# control_project.net
KiCad netlist of a schematic drawn in EAGLE
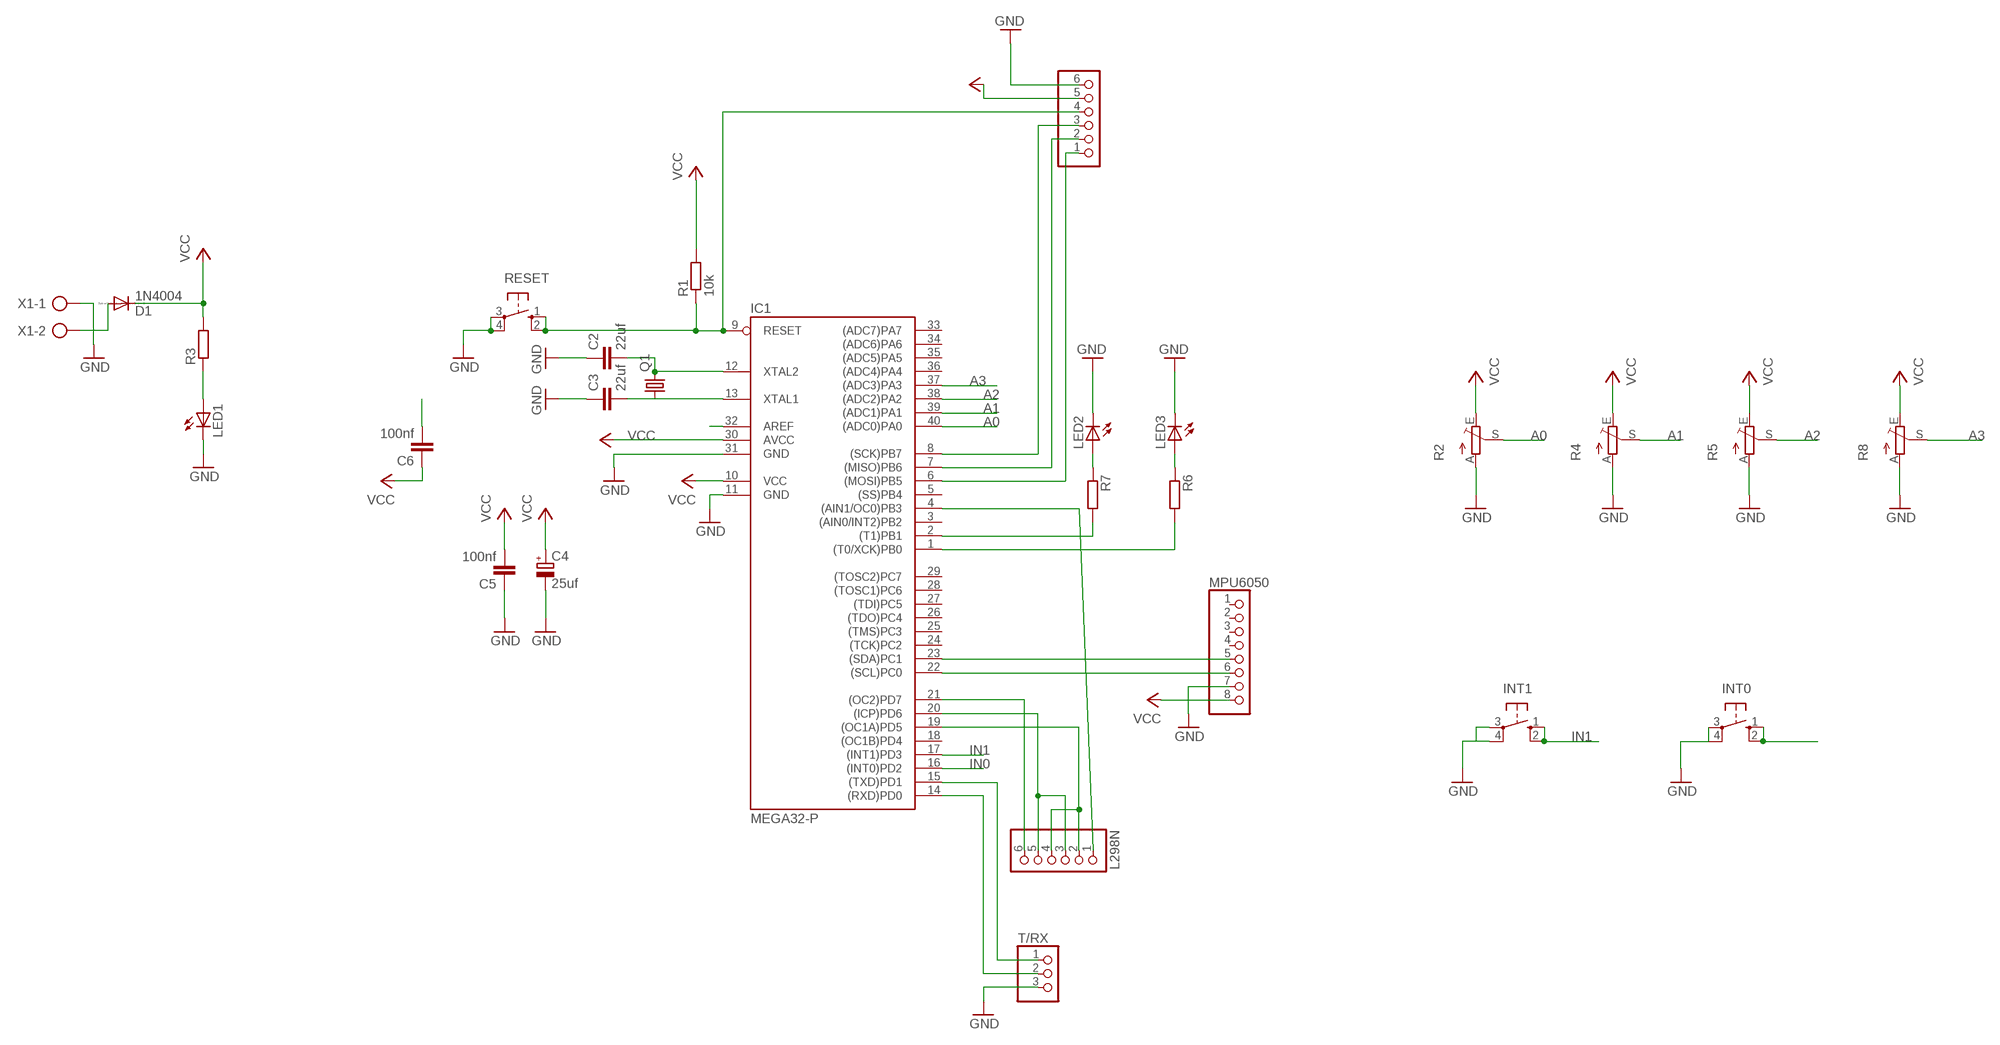
[diagram p0: schematic, sheet 1]

(export (version "E")
  (design (tool "Eeschema 10.0.6"))
  (components
    (comp (ref "C2")
      (value "22uf")
      (footprint "eagle-import:C050-025X075")
      (libsource (lib "eagle-import") (part "C-EU050-025X075"))
    )
    (comp (ref "C3")
      (value "22uf")
      (footprint "eagle-import:C050-025X075")
      (libsource (lib "eagle-import") (part "C-EU050-025X075"))
    )
    (comp (ref "C4")
      (value "25uf")
      (footprint "eagle-import:E1,8-4")
      (libsource (lib "eagle-import") (part "CPOL-EUE1.8-4"))
    )
    (comp (ref "C5")
      (value "100nf")
      (footprint "eagle-import:C050-025X075")
      (libsource (lib "eagle-import") (part "C-EU050-025X075"))
    )
    (comp (ref "C6")
      (value "100nf")
      (footprint "eagle-import:C050-025X075")
      (libsource (lib "eagle-import") (part "C-EU050-025X075"))
    )
    (comp (ref "D1")
      (value "1N4004")
      (footprint "eagle-import:DO41-10")
      (libsource (lib "eagle-import") (part "1N4004"))
    )
    (comp (ref "IC1")
      (value "MEGA32-P")
      (footprint "eagle-import:DIL40")
      (fields (field (name "MPN") "ATMEGA32-16PU"))
      (libsource (lib "eagle-import") (part "MEGA32-P"))
    )
    (comp (ref "INT0")
      (value "10-XX")
      (footprint "eagle-import:B3F-10XX")
      (fields (field (name "MPN") "B3F-1000"))
      (libsource (lib "eagle-import") (part "10-XX"))
    )
    (comp (ref "INT1")
      (value "10-XX")
      (footprint "eagle-import:B3F-10XX")
      (fields (field (name "MPN") "B3F-1000"))
      (libsource (lib "eagle-import") (part "10-XX"))
    )
    (comp (ref "L298N")
      (value "PINHD-1X6")
      (footprint "eagle-import:1X06")
      (libsource (lib "eagle-import") (part "PINHD-1X6"))
    )
    (comp (ref "LED1")
      (value "LED5MM")
      (footprint "eagle-import:LED5MM")
      (libsource (lib "eagle-import") (part "LED5MM"))
    )
    (comp (ref "LED2")
      (value "LED5MM")
      (footprint "eagle-import:LED5MM")
      (libsource (lib "eagle-import") (part "LED5MM"))
    )
    (comp (ref "LED3")
      (value "LED5MM")
      (footprint "eagle-import:LED5MM")
      (libsource (lib "eagle-import") (part "LED5MM"))
    )
    (comp (ref "MPU6050")
      (value "PINHD-1X8")
      (footprint "eagle-import:1X08")
      (libsource (lib "eagle-import") (part "PINHD-1X8"))
    )
    (comp (ref "PROG")
      (value "PINHD-1X6")
      (footprint "eagle-import:1X06")
      (libsource (lib "eagle-import") (part "PINHD-1X6"))
    )
    (comp (ref "Q1")
      (value "CRYSTALHC49U-V")
      (footprint "eagle-import:HC49U-V")
      (libsource (lib "eagle-import") (part "CRYSTALHC49U-V"))
    )
    (comp (ref "R1")
      (value "10k")
      (footprint "eagle-import:0207_7")
      (libsource (lib "eagle-import") (part "R-EU_0207/7"))
    )
    (comp (ref "R2")
      (value "TRIM_EU-RJ6")
      (footprint "eagle-import:RJ6")
      (libsource (lib "eagle-import") (part "TRIM_EU-RJ6"))
    )
    (comp (ref "R3")
      (value "R-EU_0207/7")
      (footprint "eagle-import:0207_7")
      (libsource (lib "eagle-import") (part "R-EU_0207/7"))
    )
    (comp (ref "R4")
      (value "TRIM_EU-RJ6")
      (footprint "eagle-import:RJ6")
      (libsource (lib "eagle-import") (part "TRIM_EU-RJ6"))
    )
    (comp (ref "R5")
      (value "TRIM_EU-RJ6")
      (footprint "eagle-import:RJ6")
      (libsource (lib "eagle-import") (part "TRIM_EU-RJ6"))
    )
    (comp (ref "R6")
      (value "R-EU_0207/7")
      (footprint "eagle-import:0207_7")
      (libsource (lib "eagle-import") (part "R-EU_0207/7"))
    )
    (comp (ref "R7")
      (value "R-EU_0207/7")
      (footprint "eagle-import:0207_7")
      (libsource (lib "eagle-import") (part "R-EU_0207/7"))
    )
    (comp (ref "R8")
      (value "TRIM_EU-RJ6")
      (footprint "eagle-import:RJ6")
      (libsource (lib "eagle-import") (part "TRIM_EU-RJ6"))
    )
    (comp (ref "RESET")
      (value "10-XX")
      (footprint "eagle-import:B3F-10XX")
      (fields (field (name "MPN") "B3F-1000"))
      (libsource (lib "eagle-import") (part "10-XX"))
    )
    (comp (ref "T/RX")
      (value "PINHD-1X3")
      (footprint "eagle-import:1X03")
      (libsource (lib "eagle-import") (part "PINHD-1X3"))
    )
    (comp (ref "X1")
      (value "AK300/2")
      (footprint "eagle-import:AK300_2")
      (libsource (lib "eagle-import") (part "AK300/2"))
    )
  )
  (nets
    (net (code "1") (name "/A0") (class "Default")
      (node (ref "IC1") (pin "40") (pinfunction "(ADC0)PA0_40") (pintype "bidirectional"))
      (node (ref "R2") (pin "S") (pinfunction "S_S") (pintype "passive"))
    )
    (net (code "2") (name "/A1") (class "Default")
      (node (ref "IC1") (pin "39") (pinfunction "(ADC1)PA1_39") (pintype "bidirectional"))
      (node (ref "R4") (pin "S") (pinfunction "S_S") (pintype "passive"))
    )
    (net (code "3") (name "/A2") (class "Default")
      (node (ref "IC1") (pin "38") (pinfunction "(ADC2)PA2_38") (pintype "bidirectional"))
      (node (ref "R5") (pin "S") (pinfunction "S_S") (pintype "passive"))
    )
    (net (code "4") (name "/A3") (class "Default")
      (node (ref "IC1") (pin "37") (pinfunction "(ADC3)PA3_37") (pintype "bidirectional"))
      (node (ref "R8") (pin "S") (pinfunction "S_S") (pintype "passive"))
    )
    (net (code "5") (name "/AREF") (class "Default")
      (node (ref "C6") (pin "2") (pinfunction "2_2") (pintype "passive"))
      (node (ref "IC1") (pin "32") (pinfunction "AREF_32") (pintype "passive"))
    )
    (net (code "6") (name "/IN0") (class "Default")
      (node (ref "IC1") (pin "16") (pinfunction "(INT0)PD2_16") (pintype "bidirectional"))
      (node (ref "INT0") (pin "1") (pinfunction "S_1") (pintype "passive"))
      (node (ref "INT0") (pin "2") (pinfunction "S1_2") (pintype "passive"))
    )
    (net (code "7") (name "/IN1") (class "Default")
      (node (ref "IC1") (pin "17") (pinfunction "(INT1)PD3_17") (pintype "bidirectional"))
      (node (ref "INT1") (pin "1") (pinfunction "S_1") (pintype "passive"))
      (node (ref "INT1") (pin "2") (pinfunction "S1_2") (pintype "passive"))
    )
    (net (code "8") (name "GND") (class "Default")
      (node (ref "C2") (pin "1") (pinfunction "1_1") (pintype "passive"))
      (node (ref "C3") (pin "1") (pinfunction "1_1") (pintype "passive"))
      (node (ref "C4") (pin "-") (pinfunction "-_-") (pintype "passive"))
      (node (ref "C5") (pin "1") (pinfunction "1_1") (pintype "passive"))
      (node (ref "IC1") (pin "11") (pinfunction "GND_11") (pintype "power_in"))
      (node (ref "IC1") (pin "31") (pinfunction "GND_31") (pintype "power_in"))
      (node (ref "INT0") (pin "3") (pinfunction "P_3") (pintype "passive"))
      (node (ref "INT0") (pin "4") (pinfunction "P1_4") (pintype "passive"))
      (node (ref "INT1") (pin "3") (pinfunction "P_3") (pintype "passive"))
      (node (ref "INT1") (pin "4") (pinfunction "P1_4") (pintype "passive"))
      (node (ref "LED1") (pin "K") (pinfunction "C_K") (pintype "passive"))
      (node (ref "LED2") (pin "K") (pinfunction "C_K") (pintype "passive"))
      (node (ref "LED3") (pin "K") (pinfunction "C_K") (pintype "passive"))
      (node (ref "MPU6050") (pin "7") (pinfunction "7_7") (pintype "passive"))
      (node (ref "PROG") (pin "6") (pinfunction "6_6") (pintype "passive"))
      (node (ref "R2") (pin "A") (pinfunction "A_A") (pintype "passive"))
      (node (ref "R4") (pin "A") (pinfunction "A_A") (pintype "passive"))
      (node (ref "R5") (pin "A") (pinfunction "A_A") (pintype "passive"))
      (node (ref "R8") (pin "A") (pinfunction "A_A") (pintype "passive"))
      (node (ref "RESET") (pin "3") (pinfunction "P_3") (pintype "passive"))
      (node (ref "RESET") (pin "4") (pinfunction "P1_4") (pintype "passive"))
      (node (ref "T/RX") (pin "3") (pinfunction "3_3") (pintype "passive"))
      (node (ref "X1") (pin "1") (pinfunction "KL_1") (pintype "passive"))
    )
    (net (code "9") (name "Net-(IC1-(AIN1{slash}OC0)PB3)") (class "Default")
      (node (ref "IC1") (pin "4") (pinfunction "(AIN1/OC0)PB3_4") (pintype "bidirectional"))
      (node (ref "L298N") (pin "1") (pinfunction "1_1") (pintype "passive"))
    )
    (net (code "10") (name "Net-(IC1-(ICP)PD6)") (class "Default")
      (node (ref "IC1") (pin "20") (pinfunction "(ICP)PD6_20") (pintype "bidirectional"))
      (node (ref "L298N") (pin "3") (pinfunction "3_3") (pintype "passive"))
      (node (ref "L298N") (pin "5") (pinfunction "5_5") (pintype "passive"))
    )
    (net (code "11") (name "Net-(IC1-(MISO)PB6)") (class "Default")
      (node (ref "IC1") (pin "7") (pinfunction "(MISO)PB6_7") (pintype "bidirectional"))
      (node (ref "PROG") (pin "2") (pinfunction "2_2") (pintype "passive"))
    )
    (net (code "12") (name "Net-(IC1-(MOSI)PB5)") (class "Default")
      (node (ref "IC1") (pin "6") (pinfunction "(MOSI)PB5_6") (pintype "bidirectional"))
      (node (ref "PROG") (pin "1") (pinfunction "1_1") (pintype "passive"))
    )
    (net (code "13") (name "Net-(IC1-(OC1A)PD5)") (class "Default")
      (node (ref "IC1") (pin "19") (pinfunction "(OC1A)PD5_19") (pintype "bidirectional"))
      (node (ref "L298N") (pin "2") (pinfunction "2_2") (pintype "passive"))
      (node (ref "L298N") (pin "4") (pinfunction "4_4") (pintype "passive"))
    )
    (net (code "14") (name "Net-(IC1-(OC2)PD7)") (class "Default")
      (node (ref "IC1") (pin "21") (pinfunction "(OC2)PD7_21") (pintype "bidirectional"))
      (node (ref "L298N") (pin "6") (pinfunction "6_6") (pintype "passive"))
    )
    (net (code "15") (name "Net-(IC1-(RXD)PD0)") (class "Default")
      (node (ref "IC1") (pin "14") (pinfunction "(RXD)PD0_14") (pintype "bidirectional"))
      (node (ref "T/RX") (pin "2") (pinfunction "2_2") (pintype "passive"))
    )
    (net (code "16") (name "Net-(IC1-(SCK)PB7)") (class "Default")
      (node (ref "IC1") (pin "8") (pinfunction "(SCK)PB7_8") (pintype "bidirectional"))
      (node (ref "PROG") (pin "3") (pinfunction "3_3") (pintype "passive"))
    )
    (net (code "17") (name "Net-(IC1-(SCL)PC0)") (class "Default")
      (node (ref "IC1") (pin "22") (pinfunction "(SCL)PC0_22") (pintype "bidirectional"))
      (node (ref "MPU6050") (pin "6") (pinfunction "6_6") (pintype "passive"))
    )
    (net (code "18") (name "Net-(IC1-(SDA)PC1)") (class "Default")
      (node (ref "IC1") (pin "23") (pinfunction "(SDA)PC1_23") (pintype "bidirectional"))
      (node (ref "MPU6050") (pin "5") (pinfunction "5_5") (pintype "passive"))
    )
    (net (code "19") (name "Net-(IC1-(T0{slash}XCK)PB0)") (class "Default")
      (node (ref "IC1") (pin "1") (pinfunction "(T0/XCK)PB0_1") (pintype "bidirectional"))
      (node (ref "R6") (pin "2") (pinfunction "2_2") (pintype "passive"))
    )
    (net (code "20") (name "Net-(IC1-(T1)PB1)") (class "Default")
      (node (ref "IC1") (pin "2") (pinfunction "(T1)PB1_2") (pintype "bidirectional"))
      (node (ref "R7") (pin "2") (pinfunction "2_2") (pintype "passive"))
    )
    (net (code "21") (name "Net-(IC1-(TXD)PD1)") (class "Default")
      (node (ref "IC1") (pin "15") (pinfunction "(TXD)PD1_15") (pintype "bidirectional"))
      (node (ref "T/RX") (pin "1") (pinfunction "1_1") (pintype "passive"))
    )
    (net (code "22") (name "Net-(IC1-RESET)") (class "Default")
      (node (ref "IC1") (pin "9") (pinfunction "RESET_9") (pintype "input"))
      (node (ref "PROG") (pin "4") (pinfunction "4_4") (pintype "passive"))
      (node (ref "R1") (pin "1") (pinfunction "1_1") (pintype "passive"))
      (node (ref "RESET") (pin "1") (pinfunction "S_1") (pintype "passive"))
      (node (ref "RESET") (pin "2") (pinfunction "S1_2") (pintype "passive"))
    )
    (net (code "23") (name "Net-(IC1-XTAL1)") (class "Default")
      (node (ref "C3") (pin "2") (pinfunction "2_2") (pintype "passive"))
      (node (ref "IC1") (pin "13") (pinfunction "XTAL1_13") (pintype "bidirectional"))
      (node (ref "Q1") (pin "1") (pinfunction "1_1") (pintype "passive"))
    )
    (net (code "24") (name "Net-(IC1-XTAL2)") (class "Default")
      (node (ref "C2") (pin "2") (pinfunction "2_2") (pintype "passive"))
      (node (ref "IC1") (pin "12") (pinfunction "XTAL2_12") (pintype "bidirectional"))
      (node (ref "Q1") (pin "2") (pinfunction "2_2") (pintype "passive"))
    )
    (net (code "25") (name "Net-(LED1-PadA)") (class "Default")
      (node (ref "LED1") (pin "A") (pinfunction "A_A") (pintype "passive"))
      (node (ref "R3") (pin "1") (pinfunction "1_1") (pintype "passive"))
    )
    (net (code "26") (name "Net-(LED2-PadA)") (class "Default")
      (node (ref "LED2") (pin "A") (pinfunction "A_A") (pintype "passive"))
      (node (ref "R7") (pin "1") (pinfunction "1_1") (pintype "passive"))
    )
    (net (code "27") (name "Net-(LED3-PadA)") (class "Default")
      (node (ref "LED3") (pin "A") (pinfunction "A_A") (pintype "passive"))
      (node (ref "R6") (pin "1") (pinfunction "1_1") (pintype "passive"))
    )
    (net (code "28") (name "Net-(X1B-KL)") (class "Default")
      (node (ref "D1") (pin "A") (pinfunction "A_A") (pintype "passive"))
      (node (ref "X1") (pin "2") (pinfunction "KL_2") (pintype "passive"))
    )
    (net (code "29") (name "VCC") (class "Default")
      (node (ref "C4") (pin "+") (pinfunction "+_+") (pintype "passive"))
      (node (ref "C5") (pin "2") (pinfunction "2_2") (pintype "passive"))
      (node (ref "C6") (pin "1") (pinfunction "1_1") (pintype "passive"))
      (node (ref "D1") (pin "C") (pinfunction "C_C") (pintype "passive"))
      (node (ref "IC1") (pin "10") (pinfunction "VCC_10") (pintype "power_in"))
      (node (ref "IC1") (pin "30") (pinfunction "AVCC_30") (pintype "power_in"))
      (node (ref "MPU6050") (pin "8") (pinfunction "8_8") (pintype "passive"))
      (node (ref "PROG") (pin "5") (pinfunction "5_5") (pintype "passive"))
      (node (ref "R1") (pin "2") (pinfunction "2_2") (pintype "passive"))
      (node (ref "R2") (pin "E") (pinfunction "E_E") (pintype "passive"))
      (node (ref "R3") (pin "2") (pinfunction "2_2") (pintype "passive"))
      (node (ref "R4") (pin "E") (pinfunction "E_E") (pintype "passive"))
      (node (ref "R5") (pin "E") (pinfunction "E_E") (pintype "passive"))
      (node (ref "R8") (pin "E") (pinfunction "E_E") (pintype "passive"))
    )
    (net (code "30") (name "unconnected-(IC1-(ADC4)PA4-Pad36)") (class "Default")
      (node (ref "IC1") (pin "36") (pinfunction "(ADC4)PA4_36") (pintype "bidirectional"))
    )
    (net (code "31") (name "unconnected-(IC1-(ADC5)PA5-Pad35)") (class "Default")
      (node (ref "IC1") (pin "35") (pinfunction "(ADC5)PA5_35") (pintype "bidirectional"))
    )
    (net (code "32") (name "unconnected-(IC1-(ADC6)PA6-Pad34)") (class "Default")
      (node (ref "IC1") (pin "34") (pinfunction "(ADC6)PA6_34") (pintype "bidirectional"))
    )
    (net (code "33") (name "unconnected-(IC1-(ADC7)PA7-Pad33)") (class "Default")
      (node (ref "IC1") (pin "33") (pinfunction "(ADC7)PA7_33") (pintype "bidirectional"))
    )
    (net (code "34") (name "unconnected-(IC1-(AIN0{slash}INT2)PB2-Pad3)") (class "Default")
      (node (ref "IC1") (pin "3") (pinfunction "(AIN0/INT2)PB2_3") (pintype "bidirectional"))
    )
    (net (code "35") (name "unconnected-(IC1-(OC1B)PD4-Pad18)") (class "Default")
      (node (ref "IC1") (pin "18") (pinfunction "(OC1B)PD4_18") (pintype "bidirectional"))
    )
    (net (code "36") (name "unconnected-(IC1-(SS)PB4-Pad5)") (class "Default")
      (node (ref "IC1") (pin "5") (pinfunction "(SS)PB4_5") (pintype "bidirectional"))
    )
    (net (code "37") (name "unconnected-(IC1-(TCK)PC2-Pad24)") (class "Default")
      (node (ref "IC1") (pin "24") (pinfunction "(TCK)PC2_24") (pintype "bidirectional"))
    )
    (net (code "38") (name "unconnected-(IC1-(TDI)PC5-Pad27)") (class "Default")
      (node (ref "IC1") (pin "27") (pinfunction "(TDI)PC5_27") (pintype "bidirectional"))
    )
    (net (code "39") (name "unconnected-(IC1-(TDO)PC4-Pad26)") (class "Default")
      (node (ref "IC1") (pin "26") (pinfunction "(TDO)PC4_26") (pintype "bidirectional"))
    )
    (net (code "40") (name "unconnected-(IC1-(TMS)PC3-Pad25)") (class "Default")
      (node (ref "IC1") (pin "25") (pinfunction "(TMS)PC3_25") (pintype "bidirectional"))
    )
    (net (code "41") (name "unconnected-(IC1-(TOSC1)PC6-Pad28)") (class "Default")
      (node (ref "IC1") (pin "28") (pinfunction "(TOSC1)PC6_28") (pintype "bidirectional"))
    )
    (net (code "42") (name "unconnected-(IC1-(TOSC2)PC7-Pad29)") (class "Default")
      (node (ref "IC1") (pin "29") (pinfunction "(TOSC2)PC7_29") (pintype "bidirectional"))
    )
    (net (code "43") (name "unconnected-(MPU6050-Pad1)") (class "Default")
      (node (ref "MPU6050") (pin "1") (pinfunction "1_1") (pintype "passive"))
    )
    (net (code "44") (name "unconnected-(MPU6050-Pad2)") (class "Default")
      (node (ref "MPU6050") (pin "2") (pinfunction "2_2") (pintype "passive"))
    )
    (net (code "45") (name "unconnected-(MPU6050-Pad3)") (class "Default")
      (node (ref "MPU6050") (pin "3") (pinfunction "3_3") (pintype "passive"))
    )
    (net (code "46") (name "unconnected-(MPU6050-Pad4)") (class "Default")
      (node (ref "MPU6050") (pin "4") (pinfunction "4_4") (pintype "passive"))
    )
  )
)
